# H1FR50.net
KiCad netlist of a schematic drawn in EAGLE
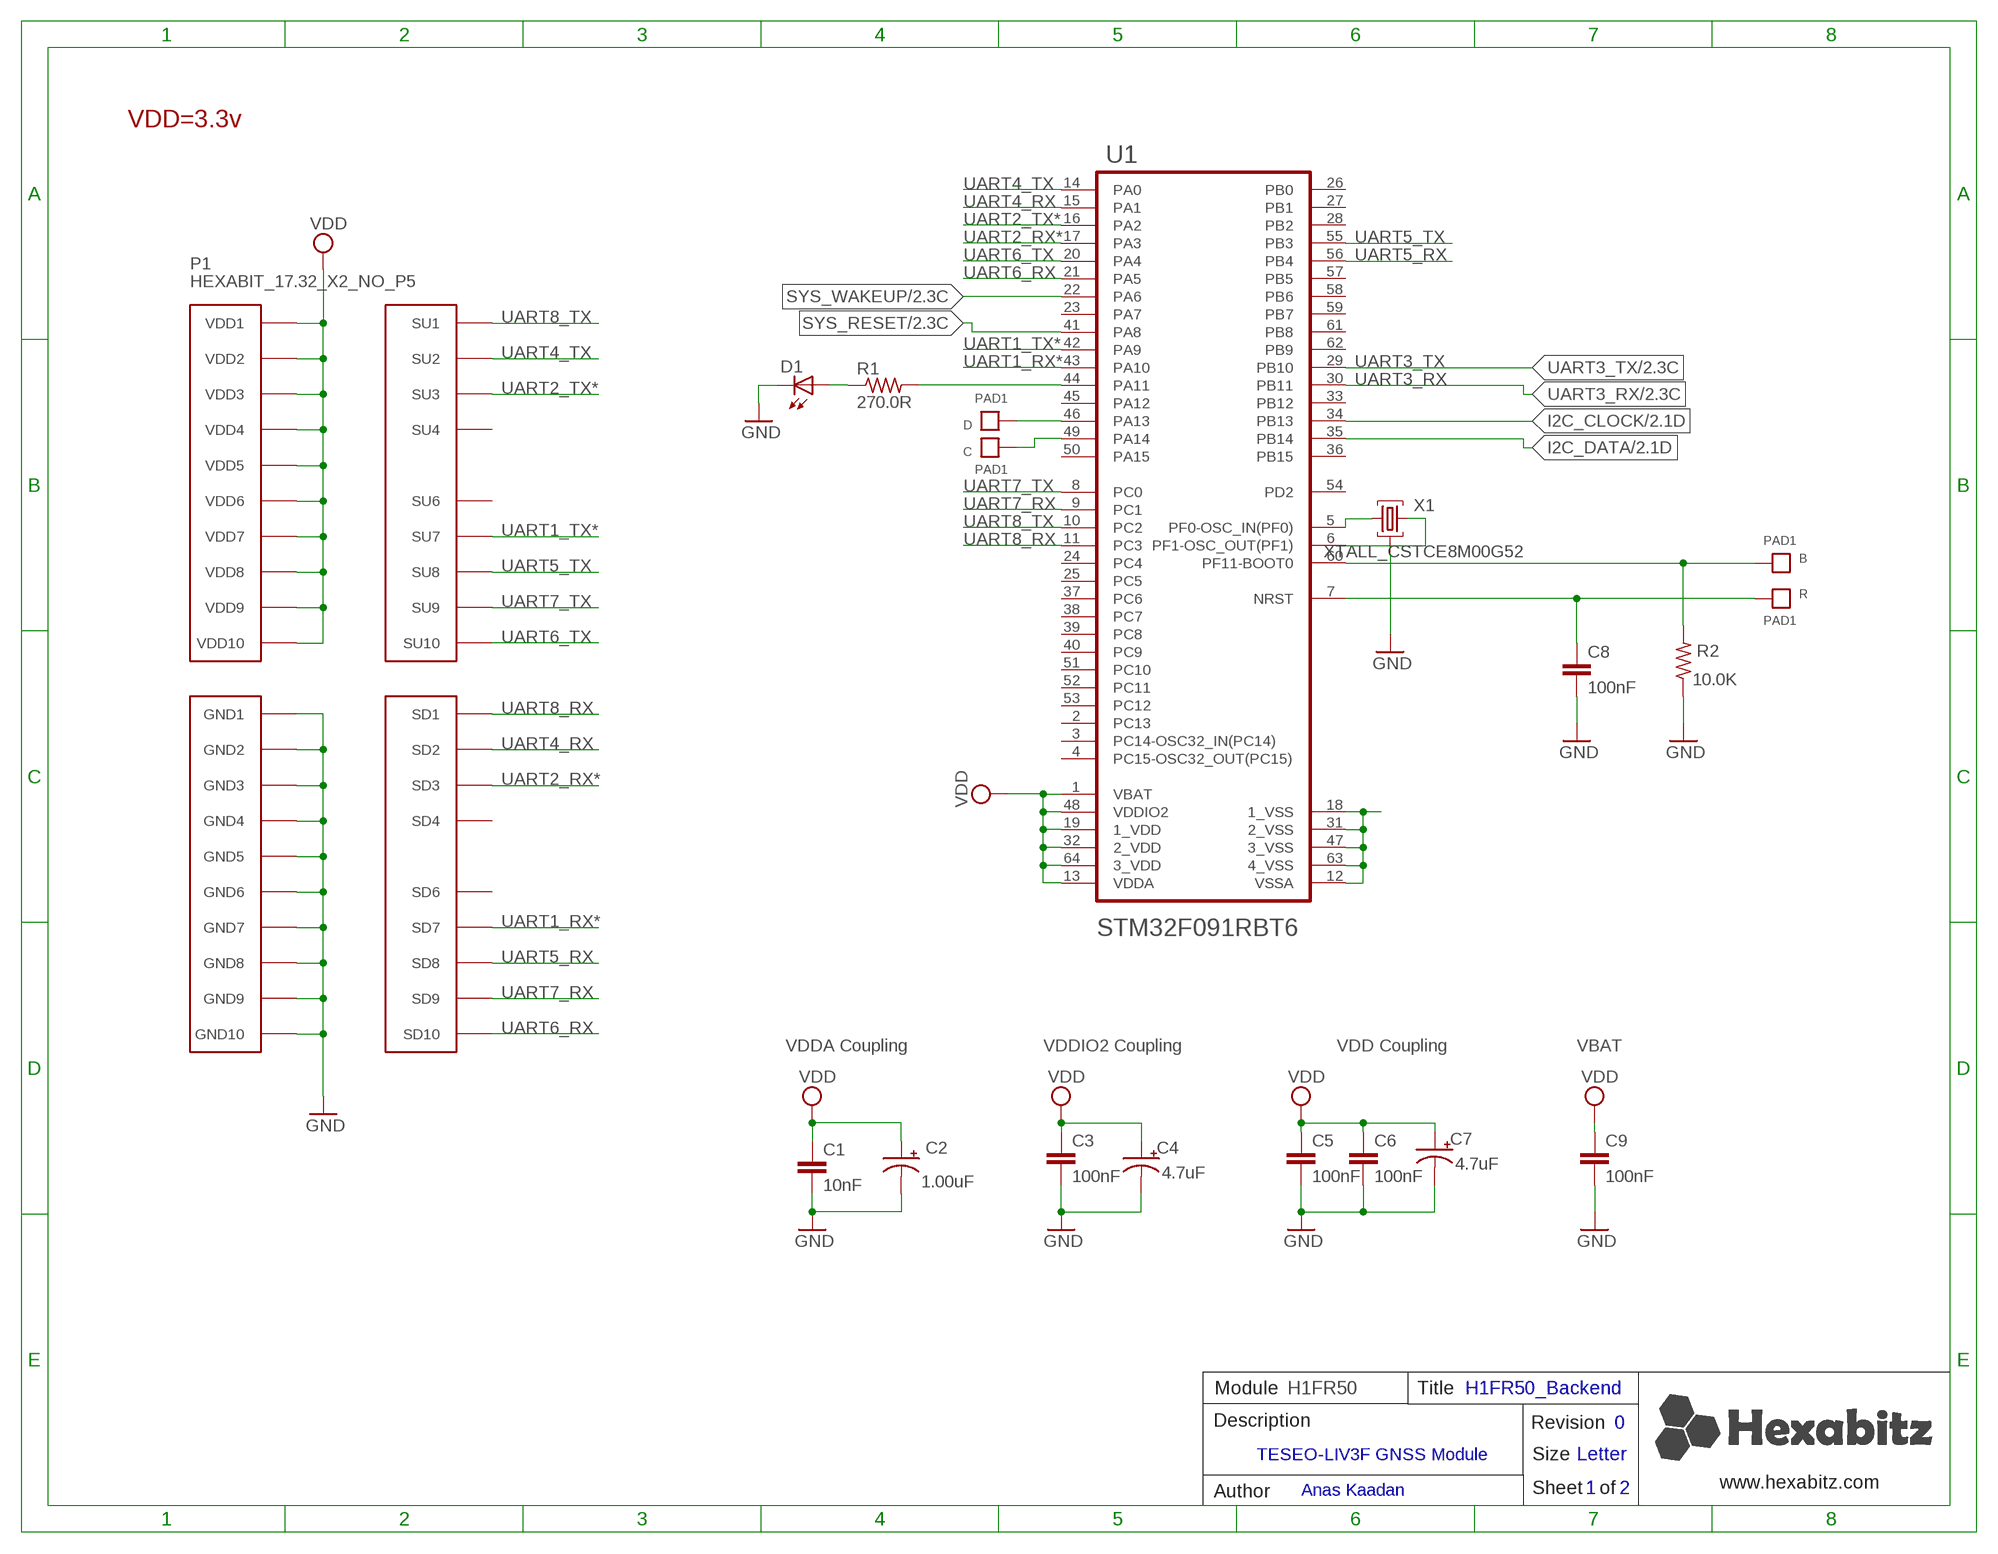
[diagram p0: schematic, sheet 1]
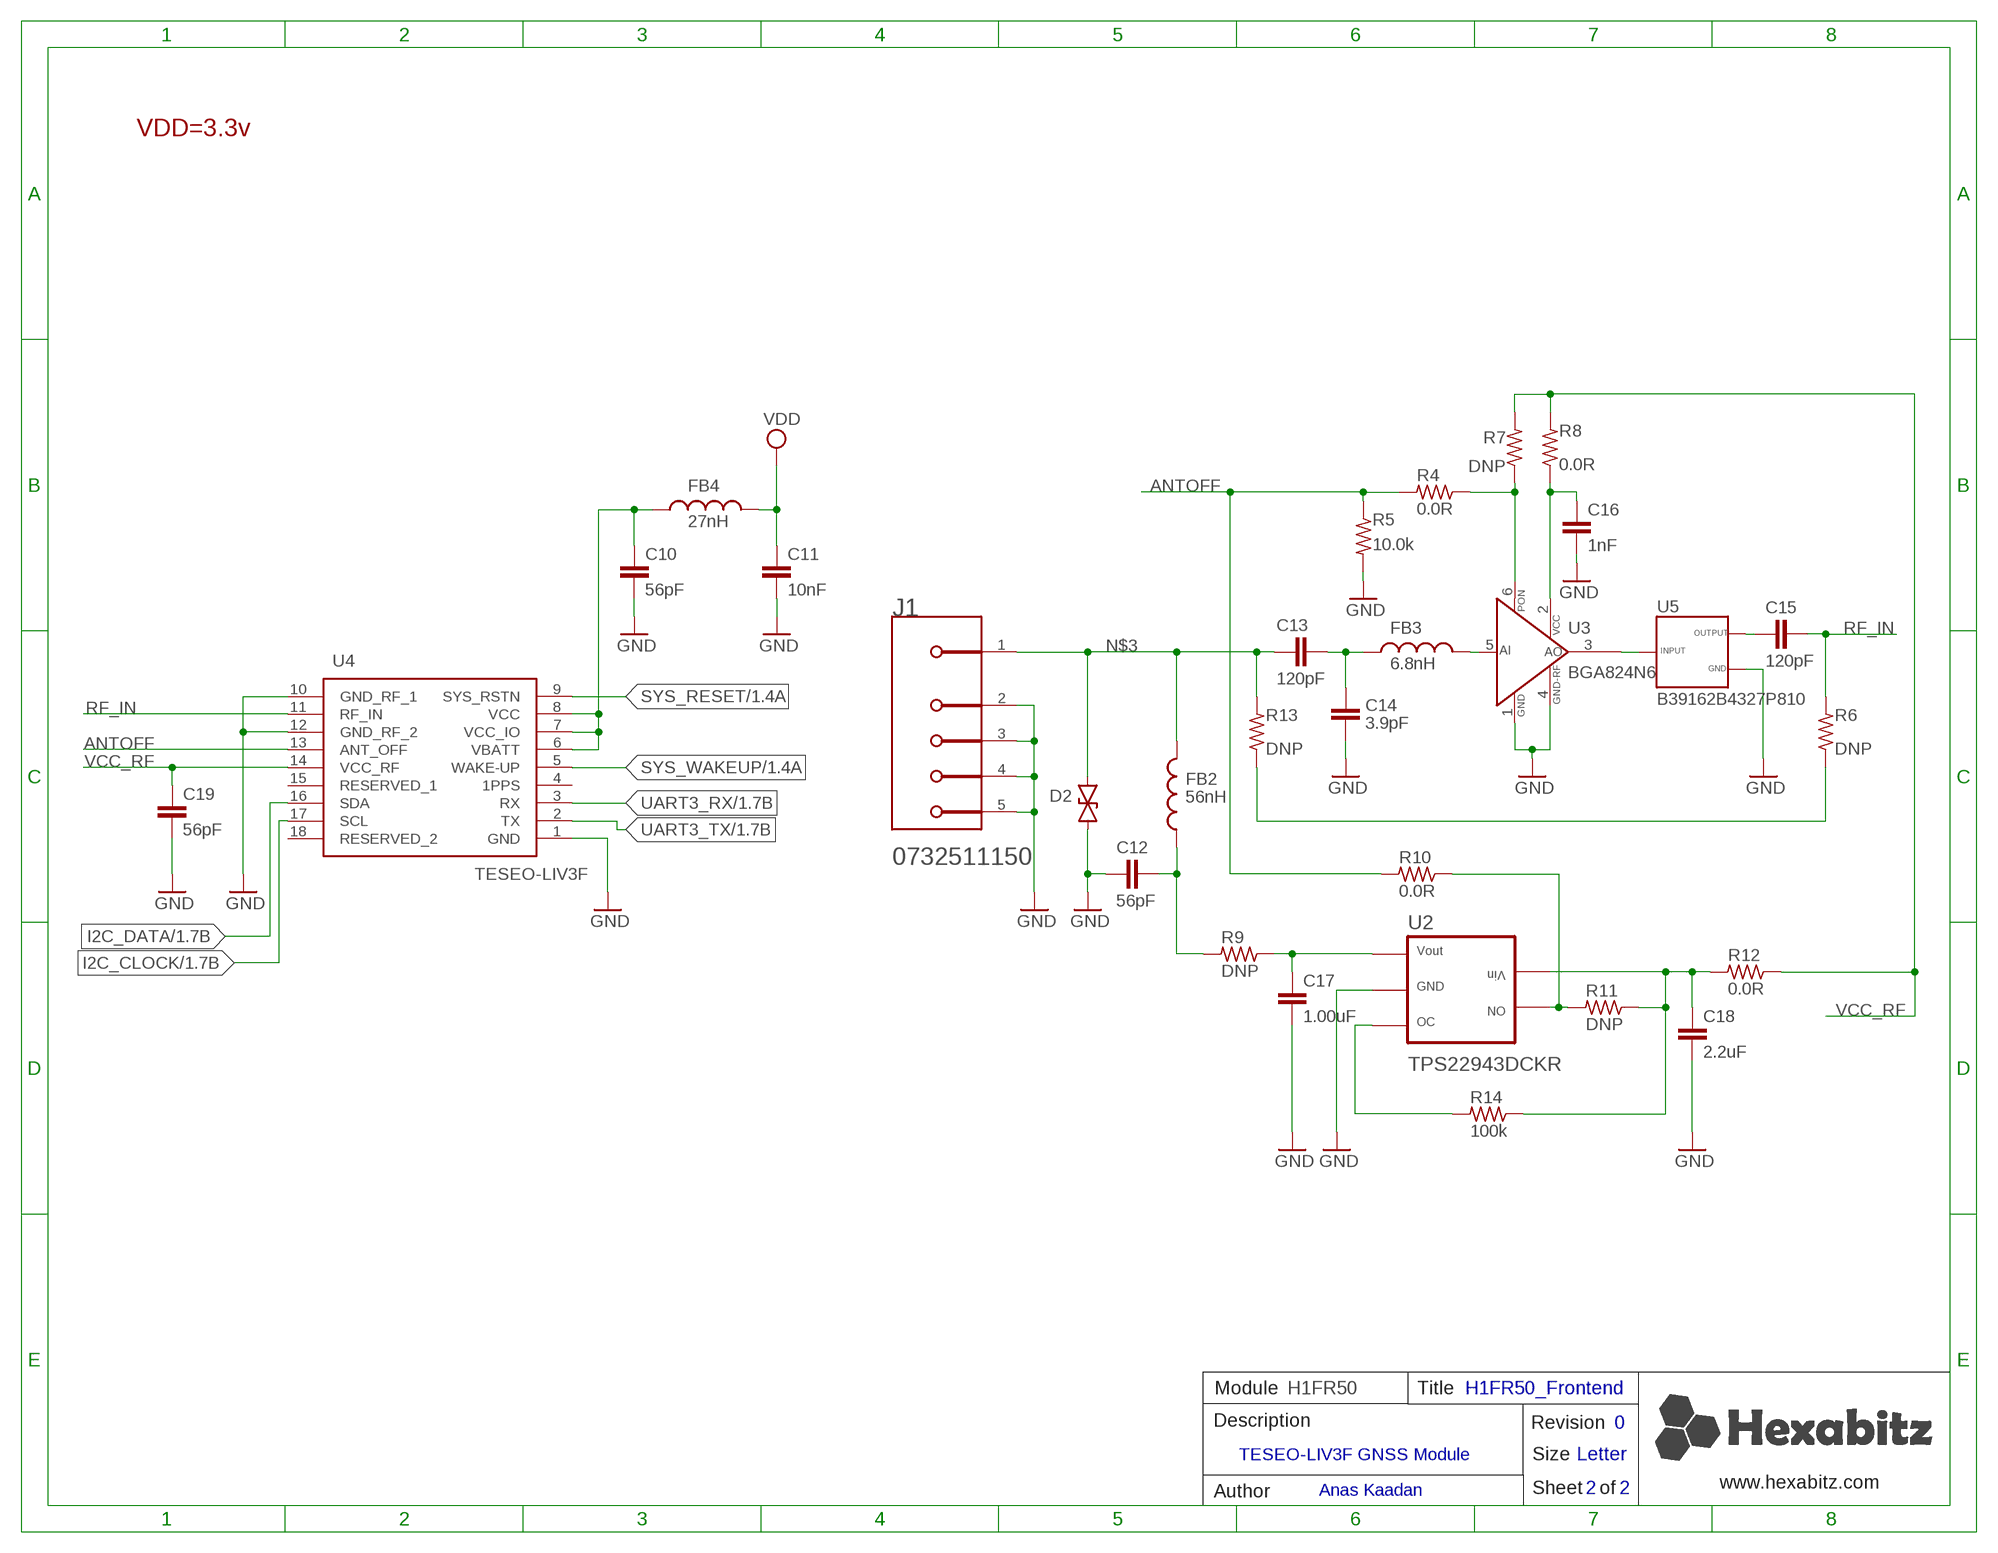
[diagram p1: schematic, sheet 2]

(export (version "E")
  (design (tool "Eeschema 10.0.6"))
  (components
    (comp (ref "C10")
      (value "56pF")
      (footprint "eagle-import:C-0201")
      (fields
        (field (name "MFN") "Murata")
        (field (name "MPN") "GRM0335C1E560GA01D")
        (field (name "OCTOPART_URL") "https://octopart.com/grm0335c1e560ga01d-murata-24611383?r=sp")
      )
      (libsource (lib "eagle-import") (part "C-0201C0201"))
    )
    (comp (ref "C11")
      (value "10nF")
      (footprint "eagle-import:C-0402")
      (fields
        (field (name "CAPACITANCE") "10nF ")
        (field (name "MFN") "TDK ")
        (field (name "MPN") "CGA2B3X7R1H103K050BE ")
        (field (name "OCTOPART_URL") "https://octopart.com/cga2b3x7r1h103k050be-tdk-68305469?r=sp ")
      )
      (libsource (lib "eagle-import") (part "C-0402"))
    )
    (comp (ref "C12")
      (value "56pF")
      (footprint "eagle-import:C-0402")
      (fields
        (field (name "CAPACITANCE") "56pF ")
        (field (name "MFN") "Murata ")
        (field (name "MPN") "GRM1555C1H560JA01D ")
        (field (name "OCTOPART_URL") "https://octopart.com/grm1555c1h560ja01d-murata-15197568?r=sp ")
      )
      (libsource (lib "eagle-import") (part "C-0402"))
    )
    (comp (ref "C13")
      (value "120pF")
      (footprint "eagle-import:C-0402")
      (fields
        (field (name "CAPACITANCE") "120pF ")
        (field (name "MFN") "Murata ")
        (field (name "MPN") "GRM1555C1H121JA01D ")
        (field (name "OCTOPART_URL") "https://octopart.com/grm1555c1h121ja01d-murata-196010?r=sp ")
      )
      (libsource (lib "eagle-import") (part "C-0402"))
    )
    (comp (ref "C14")
      (value "3.9pF")
      (footprint "eagle-import:C-0402")
      (fields
        (field (name "CAPACITANCE") "3.9pF ")
        (field (name "MFN") "Murata ")
        (field (name "MPN") "GRM1555C1H3R9WA01D ")
        (field (name "OCTOPART_URL") "https://octopart.com/grm1555c1h3r9wa01d-murata-20477997?r=sp ")
      )
      (libsource (lib "eagle-import") (part "C-0402"))
    )
    (comp (ref "C15")
      (value "120pF")
      (footprint "eagle-import:C-0402")
      (fields
        (field (name "CAPACITANCE") "120pF ")
        (field (name "MFN") "Murata ")
        (field (name "MPN") "GRM1555C1H121JA01D ")
        (field (name "OCTOPART_URL") "https://octopart.com/grm1555c1h121ja01d-murata-196010?r=sp ")
      )
      (libsource (lib "eagle-import") (part "C-0402"))
    )
    (comp (ref "C16")
      (value "1nF")
      (footprint "eagle-import:C-0402")
      (fields
        (field (name "CAPACITANCE") "1nF ")
        (field (name "MFN") "Murata ")
        (field (name "MPN") "GRM155R71H102KA01D ")
        (field (name "OCTOPART_URL") "https://octopart.com/grm155r71h102ka01d-murata-196021?r=sp ")
      )
      (libsource (lib "eagle-import") (part "C-0402"))
    )
    (comp (ref "C17")
      (value "1.00uF")
      (footprint "eagle-import:C-0402")
      (fields
        (field (name "CAPACITANCE") "1.00uF")
        (field (name "MFN") "KEMET")
        (field (name "MPN") "C0402C105K8PAC7411")
        (field (name "OCTOPART_URL") "https://octopart.com/c0402c105k8pac7411-kemet-75146233?r=sp")
      )
      (libsource (lib "eagle-import") (part "C-0402"))
    )
    (comp (ref "C18")
      (value "2.2uF")
      (footprint "eagle-import:C-0402")
      (fields
        (field (name "CAPACITANCE") "2.2uF")
        (field (name "MFN") "https://octopart.com/c0402c225k7pactu-kemet-89187402?r=sp")
        (field (name "MPN") "C0402C225K7PACTU")
        (field (name "OCTOPART_URL") "https://octopart.com/c0402c225k7pactu-kemet-89187402?r=sp")
      )
      (libsource (lib "eagle-import") (part "C-0402"))
    )
    (comp (ref "C19")
      (value "56pF")
      (footprint "eagle-import:C-0201")
      (fields
        (field (name "MFN") "Murata")
        (field (name "MPN") "GRM0335C1E560GA01D")
        (field (name "OCTOPART_URL") "https://octopart.com/grm0335c1e560ga01d-murata-24611383?r=sp")
      )
      (libsource (lib "eagle-import") (part "C-0201C0201"))
    )
    (comp (ref "D2")
      (value "ESDARF02-1BU2CK")
      (footprint "eagle-import:CAPC0201X13N")
      (libsource (lib "eagle-import") (part "ESDARF02-1BU2CK"))
    )
    (comp (ref "FB2")
      (value "56nH")
      (footprint "eagle-import:FB-0402")
      (fields (field (name "MFN") "Murata ") (field (name "MPN") "LQW15AN6N8G00D "))
      (libsource (lib "eagle-import") (part "FB-0402"))
    )
    (comp (ref "FB3")
      (value "6.8nH")
      (footprint "eagle-import:FB-0402")
      (fields (field (name "MFN") "Würth Elektronik ") (field (name "MPN") "744784156A "))
      (libsource (lib "eagle-import") (part "FB-0402"))
    )
    (comp (ref "FB4")
      (value "27nH")
      (footprint "eagle-import:FB-0402")
      (fields (field (name "MFN") "Murata ") (field (name "MPN") "LQG15HS27NJ02D "))
      (libsource (lib "eagle-import") (part "FB-0402"))
    )
    (comp (ref "J1")
      (value "MOLEX_INC_0732511150MOLEX_INC_0732511150_0_0")
      (footprint "eagle-import:MOLEX_INC_0732511150_0")
      (fields
        (field (name "DIGIKEY_PART_NUMBER") "WM5534-ND")
        (field (name "MF") "Molex Inc")
        (field (name "MPN") "0732511150")
      )
      (libsource (lib "eagle-import") (part "MOLEX_INC_0732511150MOLEX_INC_0732511150_0_0"))
    )
    (comp (ref "R4")
      (value "0.0R")
      (footprint "eagle-import:R-0402")
      (libsource (lib "eagle-import") (part "R-0402"))
    )
    (comp (ref "R5")
      (value "10.0k")
      (footprint "eagle-import:R-0402")
      (fields
        (field (name "MFN") "TE Connectivity")
        (field (name "MPN") "CRGCQ0402F10K")
        (field (name "OCTOPART_URL") "https://octopart.com/crgcq0402f10k-te+connectivity-91017932?r=sp ")
        (field (name "RESISTANCE") "10.0K ")
        (field (name "TOLERANCE") "±1% ")
      )
      (libsource (lib "eagle-import") (part "R-0402"))
    )
    (comp (ref "R6")
      (value "DNP")
      (footprint "eagle-import:R-0402")
      (libsource (lib "eagle-import") (part "R-0402"))
    )
    (comp (ref "R7")
      (value "DNP")
      (footprint "eagle-import:R-0402")
      (libsource (lib "eagle-import") (part "R-0402"))
    )
    (comp (ref "R8")
      (value "0.0R")
      (footprint "eagle-import:R-0402")
      (libsource (lib "eagle-import") (part "R-0402"))
    )
    (comp (ref "R9")
      (value "DNP")
      (footprint "eagle-import:R-0402")
      (libsource (lib "eagle-import") (part "R-0402"))
    )
    (comp (ref "R10")
      (value "0.0R")
      (footprint "eagle-import:R-0402")
      (libsource (lib "eagle-import") (part "R-0402"))
    )
    (comp (ref "R11")
      (value "DNP")
      (footprint "eagle-import:R-0402")
      (libsource (lib "eagle-import") (part "R-0402"))
    )
    (comp (ref "R12")
      (value "0.0R")
      (footprint "eagle-import:R-0402")
      (libsource (lib "eagle-import") (part "R-0402"))
    )
    (comp (ref "R13")
      (value "DNP")
      (footprint "eagle-import:R-0402")
      (libsource (lib "eagle-import") (part "R-0402"))
    )
    (comp (ref "R14")
      (value "100k")
      (footprint "eagle-import:R-0603")
      (fields
        (field (name "MFN") "Yageo ")
        (field (name "MPN") "AC0603FR-07100KL ")
        (field (name "OCTOPART_URL") "https://octopart.com/ac0603fr-07100kl-yageo-21711090?r=sp ")
        (field (name "RESISTANCE") "100k ")
        (field (name "TOLERANCE") "±1% ")
      )
      (libsource (lib "eagle-import") (part "R-0603"))
    )
    (comp (ref "U2")
      (value "TPS22943DCKR")
      (footprint "eagle-import:SOT65P210X110-5N")
      (libsource (lib "eagle-import") (part "TPS22943DCKR"))
    )
    (comp (ref "U3")
      (value "BGA824N6")
      (footprint "eagle-import:BGA824N6")
      (fields (field (name "MPN") "BGA824N6E6327XTSA1"))
      (libsource (lib "eagle-import") (part "BGA824N6"))
    )
    (comp (ref "U4")
      (value "TESEO-LIV3F")
      (footprint "eagle-import:SON110P970X1010X230-18N")
      (fields (field (name "MF") "STMicroelectronics"))
      (libsource (lib "eagle-import") (part "TESEO-LIV3F"))
    )
    (comp (ref "U5")
      (value "B39162B4327P810")
      (footprint "eagle-import:FIL_B39162B4327P810")
      (libsource (lib "eagle-import") (part "B39162B4327P810"))
    )
    (comp (ref "B")
      (value "PAD1")
      (footprint "eagle-import:PAD1")
      (libsource (lib "eagle-import") (part "PAD1"))
    )
    (comp (ref "C")
      (value "PAD1")
      (footprint "eagle-import:PAD1")
      (libsource (lib "eagle-import") (part "PAD1"))
    )
    (comp (ref "C1")
      (value "10nF")
      (footprint "eagle-import:C-0603")
      (fields
        (field (name "CAPACITANCE") "10nF")
        (field (name "MFN") "KEMET")
        (field (name "MPN") "C0603C103K5RACTU")
        (field (name "OCTOPART_URL") "https://octopart.com/c0603c103k5ractu-kemet-133094?r=sp&s=R_iPBxLnSmGqhkU2rIMFpg")
        (field (name "TOLERANCE") "10%")
        (field (name "VOLTAGE_RATING") "50V")
      )
      (libsource (lib "eagle-import") (part "C-0603"))
    )
    (comp (ref "C2")
      (value "1.00uF")
      (footprint "eagle-import:C-0805-POL")
      (fields
        (field (name "CAPACITANCE") "1.00uF")
        (field (name "MFN") "Yageo")
        (field (name "MPN") "CC0805KKX7R7BB105")
        (field (name "OCTOPART_URL") "https://octopart.com/cc0805kkx7r7bb105-yageo-8376555?r=sp&s=YKl1wwtkROau_X5nniH2ig")
        (field (name "TOLERANCE") "10%")
        (field (name "VOLTAGE_RATING") "16V")
      )
      (libsource (lib "eagle-import") (part "C-0805-POL"))
    )
    (comp (ref "C3")
      (value "100nF")
      (footprint "eagle-import:C-0603")
      (fields
        (field (name "CAPACITANCE") "100nF")
        (field (name "MFN") "KEMET")
        (field (name "MPN") "C0603C104K8RACTU")
        (field (name "OCTOPART_URL") "https://octopart.com/c0603c104k8ractu-kemet-145075?r=sp&s=9bS9ASSwSEqMCE9KBEQZ0g")
        (field (name "TOLERANCE") "10%")
        (field (name "VOLTAGE_RATING") "10V")
      )
      (libsource (lib "eagle-import") (part "C-0603"))
    )
    (comp (ref "C4")
      (value "4.7uF")
      (footprint "eagle-import:C-0805-POL")
      (fields
        (field (name "CAPACITANCE") "4.7uF")
        (field (name "MFN") "Murata")
        (field (name "MPN") "GRM21BC81E475KA12L")
        (field (name "OCTOPART_URL") "https://octopart.com/grm21bc81e475ka12l-murata-10331911?r=sp&s=RY3qZSD8T6mG6TC9CHI5qQ")
        (field (name "TOLERANCE") "10%")
        (field (name "VOLTAGE_RATING") "25V")
      )
      (libsource (lib "eagle-import") (part "C-0805-POL"))
    )
    (comp (ref "C5")
      (value "100nF")
      (footprint "eagle-import:C-0603")
      (fields
        (field (name "CAPACITANCE") "100nF")
        (field (name "MFN") "KEMET")
        (field (name "MPN") "C0603C104K8RACTU")
        (field (name "OCTOPART_URL") "https://octopart.com/c0603c104k8ractu-kemet-145075?r=sp&s=9bS9ASSwSEqMCE9KBEQZ0g")
        (field (name "TOLERANCE") "10%")
        (field (name "VOLTAGE_RATING") "10")
      )
      (libsource (lib "eagle-import") (part "C-0603"))
    )
    (comp (ref "C6")
      (value "100nF")
      (footprint "eagle-import:C-0603")
      (fields
        (field (name "CAPACITANCE") "100nF")
        (field (name "MFN") "KEMET")
        (field (name "MPN") "C0603C104K8RACTU")
        (field (name "OCTOPART_URL") "https://octopart.com/c0603c104k8ractu-kemet-145075?r=sp&s=9bS9ASSwSEqMCE9KBEQZ0g")
        (field (name "TOLERANCE") "10%")
        (field (name "VOLTAGE_RATING") "10V")
      )
      (libsource (lib "eagle-import") (part "C-0603"))
    )
    (comp (ref "C7")
      (value "4.7uF")
      (footprint "eagle-import:C-0805-POL")
      (fields
        (field (name "CAPACITANCE") "4.7uF")
        (field (name "MFN") "Murata")
        (field (name "MPN") "GRM21BC81E475KA12L")
        (field (name "OCTOPART_URL") "https://octopart.com/grm21bc81e475ka12l-murata-10331911?r=sp&s=RY3qZSD8T6mG6TC9CHI5qQ")
        (field (name "TOLERANCE") "10%")
        (field (name "VOLTAGE_RATING") "25V")
      )
      (libsource (lib "eagle-import") (part "C-0805-POL"))
    )
    (comp (ref "C8")
      (value "100nF")
      (footprint "eagle-import:C-0603")
      (fields
        (field (name "CAPACITANCE") "100nF")
        (field (name "MFN") "KEMET")
        (field (name "MPN") "C0603C104K8RACTU")
        (field (name "OCTOPART_URL") "https://octopart.com/c0603c104k8ractu-kemet-145075?r=sp&s=9bS9ASSwSEqMCE9KBEQZ0g")
        (field (name "TOLERANCE") "10%")
        (field (name "VOLTAGE_RATING") "10V")
      )
      (libsource (lib "eagle-import") (part "C-0603"))
    )
    (comp (ref "C9")
      (value "100nF")
      (footprint "eagle-import:C-0603")
      (fields
        (field (name "CAPACITANCE") "100nF")
        (field (name "MFN") "KEMET")
        (field (name "MPN") "C0603C104K8RACTU")
        (field (name "OCTOPART_URL") "https://octopart.com/c0603c104k8ractu-kemet-145075?r=sp&s=9bS9ASSwSEqMCE9KBEQZ0g")
        (field (name "TOLERANCE") "10V")
        (field (name "VOLTAGE_RATING") "10%")
      )
      (libsource (lib "eagle-import") (part "C-0603"))
    )
    (comp (ref "D")
      (value "PAD1")
      (footprint "eagle-import:PAD1")
      (libsource (lib "eagle-import") (part "PAD1"))
    )
    (comp (ref "D1")
      (value "VLMS1300-GS08")
      (footprint "eagle-import:VLMS1300-GS08")
      (fields
        (field (name "MFN") "Vishay")
        (field (name "MPN") "VLMS1300-GS08")
        (field (name "OCTOPART_URL") "https://octopart.com/vlms1300-gs08-vishay-21709201?r=sp&s=_gcP4_q8T1SC6PJQPTQ9yA")
      )
      (libsource (lib "eagle-import") (part "VLMS1300-GS08"))
    )
    (comp (ref "P1")
      (value "HEXABIT_17.32_X2_NO_P5")
      (footprint "eagle-import:HEXABIT_17.32_X2_NO_P5")
      (libsource (lib "eagle-import") (part "HEXABIT_?_X2_NO_P517.32"))
    )
    (comp (ref "R")
      (value "PAD1")
      (footprint "eagle-import:PAD1")
      (libsource (lib "eagle-import") (part "PAD1"))
    )
    (comp (ref "R1")
      (value "270.0R")
      (footprint "eagle-import:R-0603")
      (fields
        (field (name "MFN") "Yageo")
        (field (name "MPN") "RC0603FR-07270RL")
        (field (name "OCTOPART_URL") "https://octopart.com/search?q=RC0603FR-07270RL&start=0")
        (field (name "RESISTANCE") "270.0 Ohm")
        (field (name "TOLERANCE") "1%")
      )
      (libsource (lib "eagle-import") (part "Hexabitz_R-0603"))
    )
    (comp (ref "R2")
      (value "10.0K")
      (footprint "eagle-import:R-0603")
      (fields
        (field (name "MFN") "Yageo")
        (field (name "MPN") "RC0603JR-0710KL")
        (field (name "OCTOPART_URL") "https://octopart.com/search?q=RC0603JR-0710KL&start=0")
        (field (name "RESISTANCE") "10.0K Ohm")
        (field (name "TOLERANCE") "5%")
      )
      (libsource (lib "eagle-import") (part "Hexabitz_R-0603"))
    )
    (comp (ref "U1")
      (value "STM32F091RBT6STMICROELECTRONICS_STM32F091RBT6_0_1")
      (footprint "eagle-import:STMICROELECTRONICS_STM32F091RBT6_1")
      (fields (field (name "MF") "STMicroelectronics") (field (name "MPN") "STM32F091RBT6"))
      (libsource (lib "eagle-import") (part "STM32F091RBT6STMICROELECTRONICS_STM32F091RBT6_0_1"))
    )
    (comp (ref "X1")
      (value "XTALL_CSTCE8M00G52")
      (footprint "eagle-import:XTALL_CSTCE8M00G52")
      (fields (field (name "MPN") "CSTCE8M00G52Z-R0"))
      (libsource (lib "eagle-import") (part "XTALL_CSTCE8M00G52"))
    )
  )
  (nets
    (net (code "1") (name "ANTOFF") (class "Default")
      (node (ref "R10") (pin "2") (pinfunction "2_2") (pintype "passive"))
      (node (ref "R4") (pin "2") (pinfunction "2_2") (pintype "passive"))
      (node (ref "R5") (pin "1") (pinfunction "1_1") (pintype "passive"))
      (node (ref "U4") (pin "13") (pinfunction "ANT_OFF_13") (pintype "bidirectional"))
    )
    (net (code "2") (name "GND") (class "Default")
      (node (ref "C1") (pin "2") (pinfunction "2_2") (pintype "passive"))
      (node (ref "C10") (pin "1") (pinfunction "1_1") (pintype "passive"))
      (node (ref "C11") (pin "1") (pinfunction "1_1") (pintype "passive"))
      (node (ref "C12") (pin "1") (pinfunction "1_1") (pintype "passive"))
      (node (ref "C14") (pin "1") (pinfunction "1_1") (pintype "passive"))
      (node (ref "C16") (pin "2") (pinfunction "2_2") (pintype "passive"))
      (node (ref "C17") (pin "2") (pinfunction "2_2") (pintype "passive"))
      (node (ref "C18") (pin "2") (pinfunction "2_2") (pintype "passive"))
      (node (ref "C19") (pin "1") (pinfunction "1_1") (pintype "passive"))
      (node (ref "C2") (pin "2") (pinfunction "-_2") (pintype "passive"))
      (node (ref "C3") (pin "2") (pinfunction "2_2") (pintype "passive"))
      (node (ref "C4") (pin "2") (pinfunction "-_2") (pintype "passive"))
      (node (ref "C5") (pin "2") (pinfunction "2_2") (pintype "passive"))
      (node (ref "C6") (pin "2") (pinfunction "2_2") (pintype "passive"))
      (node (ref "C7") (pin "2") (pinfunction "-_2") (pintype "passive"))
      (node (ref "C8") (pin "2") (pinfunction "2_2") (pintype "passive"))
      (node (ref "C9") (pin "2") (pinfunction "2_2") (pintype "passive"))
      (node (ref "D1") (pin "C") (pinfunction "C_C") (pintype "passive"))
      (node (ref "D2") (pin "1") (pinfunction "1_1") (pintype "passive"))
      (node (ref "J1") (pin "2") (pinfunction "MNT_1_2") (pintype "passive"))
      (node (ref "J1") (pin "3") (pinfunction "MNT_2_3") (pintype "passive"))
      (node (ref "J1") (pin "4") (pinfunction "MNT_3_4") (pintype "passive"))
      (node (ref "J1") (pin "5") (pinfunction "MNT_4_5") (pintype "passive"))
      (node (ref "P1") (pin "PAD_PD11") (pinfunction "GND1_PAD_PD11") (pintype "power_in"))
      (node (ref "P1") (pin "PAD_PD12") (pinfunction "GND2_PAD_PD12") (pintype "power_in"))
      (node (ref "P1") (pin "PAD_PD13") (pinfunction "GND3_PAD_PD13") (pintype "power_in"))
      (node (ref "P1") (pin "PAD_PD14") (pinfunction "GND4_PAD_PD14") (pintype "power_in"))
      (node (ref "P1") (pin "PAD_PD15") (pinfunction "GND5_PAD_PD15") (pintype "power_in"))
      (node (ref "P1") (pin "PAD_PD16") (pinfunction "GND6_PAD_PD16") (pintype "power_in"))
      (node (ref "P1") (pin "PAD_PD17") (pinfunction "GND7_PAD_PD17") (pintype "power_in"))
      (node (ref "P1") (pin "PAD_PD18") (pinfunction "GND8_PAD_PD18") (pintype "power_in"))
      (node (ref "P1") (pin "PAD_PD19") (pinfunction "GND9_PAD_PD19") (pintype "power_in"))
      (node (ref "P1") (pin "PAD_PD20") (pinfunction "GND10_PAD_PD20") (pintype "power_in"))
      (node (ref "R2") (pin "1") (pinfunction "1_1") (pintype "passive"))
      (node (ref "R5") (pin "2") (pinfunction "2_2") (pintype "passive"))
      (node (ref "U1") (pin "12") (pinfunction "VSSA_12") (pintype "power_in"))
      (node (ref "U1") (pin "18") (pinfunction "1_VSS_18") (pintype "power_in"))
      (node (ref "U1") (pin "31") (pinfunction "2_VSS_31") (pintype "power_in"))
      (node (ref "U1") (pin "47") (pinfunction "3_VSS_47") (pintype "power_in"))
      (node (ref "U1") (pin "63") (pinfunction "4_VSS_63") (pintype "power_in"))
      (node (ref "U2") (pin "2") (pinfunction "GND_2") (pintype "power_in"))
      (node (ref "U3") (pin "1") (pinfunction "GND_1") (pintype "input"))
      (node (ref "U3") (pin "4") (pinfunction "GND-RF_4") (pintype "passive"))
      (node (ref "U4") (pin "1") (pinfunction "GND_1") (pintype "bidirectional"))
      (node (ref "U4") (pin "10") (pinfunction "GND_RF_1_10") (pintype "bidirectional"))
      (node (ref "U4") (pin "12") (pinfunction "GND_RF_2_12") (pintype "bidirectional"))
      (node (ref "U5") (pin "2") (pinfunction "GND_2") (pintype "power_in"))
      (node (ref "U5") (pin "3") (pinfunction "GND_3") (pintype "power_in"))
      (node (ref "U5") (pin "5") (pinfunction "GND_5") (pintype "power_in"))
      (node (ref "X1") (pin "P$2") (pinfunction "2_P$2") (pintype "passive"))
    )
    (net (code "3") (name "I2C_CLOCK") (class "Default")
      (node (ref "U1") (pin "34") (pinfunction "PB13_34") (pintype "bidirectional"))
      (node (ref "U4") (pin "17") (pinfunction "SCL_17") (pintype "bidirectional"))
    )
    (net (code "4") (name "I2C_DATA") (class "Default")
      (node (ref "U1") (pin "35") (pinfunction "PB14_35") (pintype "bidirectional"))
      (node (ref "U4") (pin "16") (pinfunction "SDA_16") (pintype "bidirectional"))
    )
    (net (code "5") (name "N$3") (class "Default")
      (node (ref "C13") (pin "1") (pinfunction "1_1") (pintype "passive"))
      (node (ref "D2") (pin "2") (pinfunction "2_2") (pintype "passive"))
      (node (ref "FB2") (pin "2") (pinfunction "2_2") (pintype "passive"))
      (node (ref "J1") (pin "1") (pinfunction "1_1") (pintype "passive"))
      (node (ref "R13") (pin "2") (pinfunction "2_2") (pintype "passive"))
    )
    (net (code "6") (name "Net-(C12-Pad2)") (class "Default")
      (node (ref "C12") (pin "2") (pinfunction "2_2") (pintype "passive"))
      (node (ref "FB2") (pin "1") (pinfunction "1_1") (pintype "passive"))
      (node (ref "R9") (pin "2") (pinfunction "2_2") (pintype "passive"))
    )
    (net (code "7") (name "Net-(C13-Pad2)") (class "Default")
      (node (ref "C13") (pin "2") (pinfunction "2_2") (pintype "passive"))
      (node (ref "C14") (pin "2") (pinfunction "2_2") (pintype "passive"))
      (node (ref "FB3") (pin "1") (pinfunction "1_1") (pintype "passive"))
    )
    (net (code "8") (name "Net-(D1-PadA)") (class "Default")
      (node (ref "D1") (pin "A") (pinfunction "A_A") (pintype "passive"))
      (node (ref "R1") (pin "1") (pinfunction "1_1") (pintype "passive"))
    )
    (net (code "9") (name "Net-(R13-Pad1)") (class "Default")
      (node (ref "R13") (pin "1") (pinfunction "1_1") (pintype "passive"))
      (node (ref "R6") (pin "1") (pinfunction "1_1") (pintype "passive"))
    )
    (net (code "10") (name "Net-(U1-NRST)") (class "Default")
      (node (ref "C8") (pin "1") (pinfunction "1_1") (pintype "passive"))
      (node (ref "R") (pin "P$1") (pinfunction "P$1_P$1") (pintype "passive"))
      (node (ref "R") (pin "P$2") (pinfunction "P$1_P$2") (pintype "passive"))
      (node (ref "U1") (pin "7") (pinfunction "NRST_7") (pintype "bidirectional"))
    )
    (net (code "11") (name "Net-(U1-PA11)") (class "Default")
      (node (ref "R1") (pin "2") (pinfunction "2_2") (pintype "passive"))
      (node (ref "U1") (pin "44") (pinfunction "PA11_44") (pintype "bidirectional"))
    )
    (net (code "12") (name "Net-(U1-PA13)") (class "Default")
      (node (ref "D") (pin "P$1") (pinfunction "P$1_P$1") (pintype "passive"))
      (node (ref "D") (pin "P$2") (pinfunction "P$1_P$2") (pintype "passive"))
      (node (ref "U1") (pin "46") (pinfunction "PA13_46") (pintype "bidirectional"))
    )
    (net (code "13") (name "Net-(U1-PA14)") (class "Default")
      (node (ref "C") (pin "P$1") (pinfunction "P$1_P$1") (pintype "passive"))
      (node (ref "C") (pin "P$2") (pinfunction "P$1_P$2") (pintype "passive"))
      (node (ref "U1") (pin "49") (pinfunction "PA14_49") (pintype "bidirectional"))
    )
    (net (code "14") (name "Net-(U1-PF0-OSC_IN(PF0))") (class "Default")
      (node (ref "U1") (pin "5") (pinfunction "PF0-OSC_IN(PF0)_5") (pintype "bidirectional"))
      (node (ref "X1") (pin "P$1") (pinfunction "1_P$1") (pintype "passive"))
    )
    (net (code "15") (name "Net-(U1-PF1-OSC_OUT(PF1))") (class "Default")
      (node (ref "U1") (pin "6") (pinfunction "PF1-OSC_OUT(PF1)_6") (pintype "bidirectional"))
      (node (ref "X1") (pin "P$3") (pinfunction "3_P$3") (pintype "passive"))
    )
    (net (code "16") (name "Net-(U1-PF11-BOOT0)") (class "Default")
      (node (ref "B") (pin "P$1") (pinfunction "P$1_P$1") (pintype "passive"))
      (node (ref "B") (pin "P$2") (pinfunction "P$1_P$2") (pintype "passive"))
      (node (ref "R2") (pin "2") (pinfunction "2_2") (pintype "passive"))
      (node (ref "U1") (pin "60") (pinfunction "PF11-BOOT0_60") (pintype "bidirectional"))
    )
    (net (code "17") (name "Net-(U2-OC)") (class "Default")
      (node (ref "R14") (pin "2") (pinfunction "2_2") (pintype "passive"))
      (node (ref "U2") (pin "3") (pinfunction "OC_3") (pintype "output"))
    )
    (net (code "18") (name "Net-(U2-ON)") (class "Default")
      (node (ref "R10") (pin "1") (pinfunction "1_1") (pintype "passive"))
      (node (ref "R11") (pin "2") (pinfunction "2_2") (pintype "passive"))
      (node (ref "U2") (pin "4") (pinfunction "ON_4") (pintype "input"))
    )
    (net (code "19") (name "Net-(U2-VIN)") (class "Default")
      (node (ref "C18") (pin "1") (pinfunction "1_1") (pintype "passive"))
      (node (ref "R11") (pin "1") (pinfunction "1_1") (pintype "passive"))
      (node (ref "R12") (pin "2") (pinfunction "2_2") (pintype "passive"))
      (node (ref "R14") (pin "1") (pinfunction "1_1") (pintype "passive"))
      (node (ref "U2") (pin "5") (pinfunction "VIN_5") (pintype "input"))
    )
    (net (code "20") (name "Net-(U2-VOUT)") (class "Default")
      (node (ref "C17") (pin "1") (pinfunction "1_1") (pintype "passive"))
      (node (ref "R9") (pin "1") (pinfunction "1_1") (pintype "passive"))
      (node (ref "U2") (pin "1") (pinfunction "VOUT_1") (pintype "output"))
    )
    (net (code "21") (name "Net-(U3-AI)") (class "Default")
      (node (ref "FB3") (pin "2") (pinfunction "2_2") (pintype "passive"))
      (node (ref "U3") (pin "5") (pinfunction "AI_5") (pintype "input"))
    )
    (net (code "22") (name "Net-(U3-AO)") (class "Default")
      (node (ref "U3") (pin "3") (pinfunction "AO_3") (pintype "output"))
      (node (ref "U5") (pin "1") (pinfunction "INPUT_1") (pintype "input"))
    )
    (net (code "23") (name "Net-(U3-PON)") (class "Default")
      (node (ref "R4") (pin "1") (pinfunction "1_1") (pintype "passive"))
      (node (ref "R7") (pin "1") (pinfunction "1_1") (pintype "passive"))
      (node (ref "U3") (pin "6") (pinfunction "PON_6") (pintype "input"))
    )
    (net (code "24") (name "Net-(U3-VCC)") (class "Default")
      (node (ref "C16") (pin "1") (pinfunction "1_1") (pintype "passive"))
      (node (ref "R8") (pin "1") (pinfunction "1_1") (pintype "passive"))
      (node (ref "U3") (pin "2") (pinfunction "VCC_2") (pintype "passive"))
    )
    (net (code "25") (name "Net-(U4-VBATT)") (class "Default")
      (node (ref "C10") (pin "2") (pinfunction "2_2") (pintype "passive"))
      (node (ref "FB4") (pin "1") (pinfunction "1_1") (pintype "passive"))
      (node (ref "U4") (pin "6") (pinfunction "VBATT_6") (pintype "bidirectional"))
      (node (ref "U4") (pin "7") (pinfunction "VCC_IO_7") (pintype "bidirectional"))
      (node (ref "U4") (pin "8") (pinfunction "VCC_8") (pintype "bidirectional"))
    )
    (net (code "26") (name "Net-(U5-OUTPUT)") (class "Default")
      (node (ref "C15") (pin "1") (pinfunction "1_1") (pintype "passive"))
      (node (ref "U5") (pin "4") (pinfunction "OUTPUT_4") (pintype "output"))
    )
    (net (code "27") (name "RF_IN") (class "Default")
      (node (ref "C15") (pin "2") (pinfunction "2_2") (pintype "passive"))
      (node (ref "R6") (pin "2") (pinfunction "2_2") (pintype "passive"))
      (node (ref "U4") (pin "11") (pinfunction "RF_IN_11") (pintype "bidirectional"))
    )
    (net (code "28") (name "SYS_RESET") (class "Default")
      (node (ref "U1") (pin "41") (pinfunction "PA8_41") (pintype "bidirectional"))
      (node (ref "U4") (pin "9") (pinfunction "SYS_RSTN_9") (pintype "bidirectional"))
    )
    (net (code "29") (name "SYS_WAKEUP") (class "Default")
      (node (ref "U1") (pin "22") (pinfunction "PA6_22") (pintype "bidirectional"))
      (node (ref "U4") (pin "5") (pinfunction "WAKE-UP_5") (pintype "bidirectional"))
    )
    (net (code "30") (name "UART1_RX*") (class "Default")
      (node (ref "P1") (pin "PAD_PD7") (pinfunction "SD7_PAD_PD7") (pintype "bidirectional"))
      (node (ref "U1") (pin "43") (pinfunction "PA10_43") (pintype "bidirectional"))
    )
    (net (code "31") (name "UART1_TX*") (class "Default")
      (node (ref "P1") (pin "PAD_PU7") (pinfunction "SU7_PAD_PU7") (pintype "bidirectional"))
      (node (ref "U1") (pin "42") (pinfunction "PA9_42") (pintype "bidirectional"))
    )
    (net (code "32") (name "UART2_RX*") (class "Default")
      (node (ref "P1") (pin "PAD_PD3") (pinfunction "SD3_PAD_PD3") (pintype "bidirectional"))
      (node (ref "U1") (pin "17") (pinfunction "PA3_17") (pintype "bidirectional"))
    )
    (net (code "33") (name "UART2_TX*") (class "Default")
      (node (ref "P1") (pin "PAD_PU3") (pinfunction "SU3_PAD_PU3") (pintype "bidirectional"))
      (node (ref "U1") (pin "16") (pinfunction "PA2_16") (pintype "bidirectional"))
    )
    (net (code "34") (name "UART3_RX") (class "Default")
      (node (ref "U1") (pin "30") (pinfunction "PB11_30") (pintype "bidirectional"))
      (node (ref "U4") (pin "3") (pinfunction "RX_3") (pintype "bidirectional"))
    )
    (net (code "35") (name "UART3_TX") (class "Default")
      (node (ref "U1") (pin "29") (pinfunction "PB10_29") (pintype "bidirectional"))
      (node (ref "U4") (pin "2") (pinfunction "TX_2") (pintype "bidirectional"))
    )
    (net (code "36") (name "UART4_RX") (class "Default")
      (node (ref "P1") (pin "PAD_PD2") (pinfunction "SD2_PAD_PD2") (pintype "bidirectional"))
      (node (ref "U1") (pin "15") (pinfunction "PA1_15") (pintype "bidirectional"))
    )
    (net (code "37") (name "UART4_TX") (class "Default")
      (node (ref "P1") (pin "PAD_PU2") (pinfunction "SU2_PAD_PU2") (pintype "bidirectional"))
      (node (ref "U1") (pin "14") (pinfunction "PA0_14") (pintype "bidirectional"))
    )
    (net (code "38") (name "UART5_RX") (class "Default")
      (node (ref "P1") (pin "PAD_PD8") (pinfunction "SD8_PAD_PD8") (pintype "bidirectional"))
      (node (ref "U1") (pin "56") (pinfunction "PB4_56") (pintype "bidirectional"))
    )
    (net (code "39") (name "UART5_TX") (class "Default")
      (node (ref "P1") (pin "PAD_PU8") (pinfunction "SU8_PAD_PU8") (pintype "bidirectional"))
      (node (ref "U1") (pin "55") (pinfunction "PB3_55") (pintype "bidirectional"))
    )
    (net (code "40") (name "UART6_RX") (class "Default")
      (node (ref "P1") (pin "PAD_PD10") (pinfunction "SD10_PAD_PD10") (pintype "bidirectional"))
      (node (ref "U1") (pin "21") (pinfunction "PA5_21") (pintype "bidirectional"))
    )
    (net (code "41") (name "UART6_TX") (class "Default")
      (node (ref "P1") (pin "PAD_PU10") (pinfunction "SU10_PAD_PU10") (pintype "bidirectional"))
      (node (ref "U1") (pin "20") (pinfunction "PA4_20") (pintype "bidirectional"))
    )
    (net (code "42") (name "UART7_RX") (class "Default")
      (node (ref "P1") (pin "PAD_PD9") (pinfunction "SD9_PAD_PD9") (pintype "bidirectional"))
      (node (ref "U1") (pin "9") (pinfunction "PC1_9") (pintype "bidirectional"))
    )
    (net (code "43") (name "UART7_TX") (class "Default")
      (node (ref "P1") (pin "PAD_PU9") (pinfunction "SU9_PAD_PU9") (pintype "bidirectional"))
      (node (ref "U1") (pin "8") (pinfunction "PC0_8") (pintype "bidirectional"))
    )
    (net (code "44") (name "UART8_RX") (class "Default")
      (node (ref "P1") (pin "PAD_PD1") (pinfunction "SD1_PAD_PD1") (pintype "bidirectional"))
      (node (ref "U1") (pin "11") (pinfunction "PC3_11") (pintype "bidirectional"))
    )
    (net (code "45") (name "UART8_TX") (class "Default")
      (node (ref "P1") (pin "PAD_PU1") (pinfunction "SU1_PAD_PU1") (pintype "bidirectional"))
      (node (ref "U1") (pin "10") (pinfunction "PC2_10") (pintype "bidirectional"))
    )
    (net (code "46") (name "VCC_RF") (class "Default")
      (node (ref "C19") (pin "2") (pinfunction "2_2") (pintype "passive"))
      (node (ref "R12") (pin "1") (pinfunction "1_1") (pintype "passive"))
      (node (ref "R7") (pin "2") (pinfunction "2_2") (pintype "passive"))
      (node (ref "R8") (pin "2") (pinfunction "2_2") (pintype "passive"))
      (node (ref "U4") (pin "14") (pinfunction "VCC_RF_14") (pintype "bidirectional"))
    )
    (net (code "47") (name "VDD") (class "Default")
      (node (ref "C1") (pin "1") (pinfunction "1_1") (pintype "passive"))
      (node (ref "C11") (pin "2") (pinfunction "2_2") (pintype "passive"))
      (node (ref "C2") (pin "1") (pinfunction "+_1") (pintype "passive"))
      (node (ref "C3") (pin "1") (pinfunction "1_1") (pintype "passive"))
      (node (ref "C4") (pin "1") (pinfunction "+_1") (pintype "passive"))
      (node (ref "C5") (pin "1") (pinfunction "1_1") (pintype "passive"))
      (node (ref "C6") (pin "1") (pinfunction "1_1") (pintype "passive"))
      (node (ref "C7") (pin "1") (pinfunction "+_1") (pintype "passive"))
      (node (ref "C9") (pin "1") (pinfunction "1_1") (pintype "passive"))
      (node (ref "FB4") (pin "2") (pinfunction "2_2") (pintype "passive"))
      (node (ref "P1") (pin "PAD_PU11") (pinfunction "VDD1_PAD_PU11") (pintype "power_in"))
      (node (ref "P1") (pin "PAD_PU12") (pinfunction "VDD2_PAD_PU12") (pintype "power_in"))
      (node (ref "P1") (pin "PAD_PU13") (pinfunction "VDD3_PAD_PU13") (pintype "power_in"))
      (node (ref "P1") (pin "PAD_PU14") (pinfunction "VDD4_PAD_PU14") (pintype "power_in"))
      (node (ref "P1") (pin "PAD_PU15") (pinfunction "VDD5_PAD_PU15") (pintype "power_in"))
      (node (ref "P1") (pin "PAD_PU16") (pinfunction "VDD6_PAD_PU16") (pintype "power_in"))
      (node (ref "P1") (pin "PAD_PU17") (pinfunction "VDD7_PAD_PU17") (pintype "power_in"))
      (node (ref "P1") (pin "PAD_PU18") (pinfunction "VDD8_PAD_PU18") (pintype "power_in"))
      (node (ref "P1") (pin "PAD_PU19") (pinfunction "VDD9_PAD_PU19") (pintype "power_in"))
      (node (ref "P1") (pin "PAD_PU20") (pinfunction "VDD10_PAD_PU20") (pintype "power_in"))
      (node (ref "U1") (pin "1") (pinfunction "VBAT_1") (pintype "power_in"))
      (node (ref "U1") (pin "13") (pinfunction "VDDA_13") (pintype "power_in"))
      (node (ref "U1") (pin "19") (pinfunction "1_VDD_19") (pintype "power_in"))
      (node (ref "U1") (pin "32") (pinfunction "2_VDD_32") (pintype "power_in"))
      (node (ref "U1") (pin "48") (pinfunction "VDDIO2_48") (pintype "power_in"))
      (node (ref "U1") (pin "64") (pinfunction "3_VDD_64") (pintype "power_in"))
    )
    (net (code "48") (name "unconnected-(P1-SD4-PadPAD_PD4)") (class "Default")
      (node (ref "P1") (pin "PAD_PD4") (pinfunction "SD4_PAD_PD4") (pintype "bidirectional"))
    )
    (net (code "49") (name "unconnected-(P1-SD6-PadPAD_PD6)") (class "Default")
      (node (ref "P1") (pin "PAD_PD6") (pinfunction "SD6_PAD_PD6") (pintype "bidirectional"))
    )
    (net (code "50") (name "unconnected-(P1-SU4-PadPAD_PU4)") (class "Default")
      (node (ref "P1") (pin "PAD_PU4") (pinfunction "SU4_PAD_PU4") (pintype "bidirectional"))
    )
    (net (code "51") (name "unconnected-(P1-SU6-PadPAD_PU6)") (class "Default")
      (node (ref "P1") (pin "PAD_PU6") (pinfunction "SU6_PAD_PU6") (pintype "bidirectional"))
    )
    (net (code "52") (name "unconnected-(U1-PA7-Pad23)") (class "Default")
      (node (ref "U1") (pin "23") (pinfunction "PA7_23") (pintype "bidirectional"))
    )
    (net (code "53") (name "unconnected-(U1-PA12-Pad45)") (class "Default")
      (node (ref "U1") (pin "45") (pinfunction "PA12_45") (pintype "bidirectional"))
    )
    (net (code "54") (name "unconnected-(U1-PA15-Pad50)") (class "Default")
      (node (ref "U1") (pin "50") (pinfunction "PA15_50") (pintype "bidirectional"))
    )
    (net (code "55") (name "unconnected-(U1-PB0-Pad26)") (class "Default")
      (node (ref "U1") (pin "26") (pinfunction "PB0_26") (pintype "bidirectional"))
    )
    (net (code "56") (name "unconnected-(U1-PB1-Pad27)") (class "Default")
      (node (ref "U1") (pin "27") (pinfunction "PB1_27") (pintype "bidirectional"))
    )
    (net (code "57") (name "unconnected-(U1-PB2-Pad28)") (class "Default")
      (node (ref "U1") (pin "28") (pinfunction "PB2_28") (pintype "bidirectional"))
    )
    (net (code "58") (name "unconnected-(U1-PB5-Pad57)") (class "Default")
      (node (ref "U1") (pin "57") (pinfunction "PB5_57") (pintype "bidirectional"))
    )
    (net (code "59") (name "unconnected-(U1-PB6-Pad58)") (class "Default")
      (node (ref "U1") (pin "58") (pinfunction "PB6_58") (pintype "bidirectional"))
    )
    (net (code "60") (name "unconnected-(U1-PB7-Pad59)") (class "Default")
      (node (ref "U1") (pin "59") (pinfunction "PB7_59") (pintype "bidirectional"))
    )
    (net (code "61") (name "unconnected-(U1-PB8-Pad61)") (class "Default")
      (node (ref "U1") (pin "61") (pinfunction "PB8_61") (pintype "bidirectional"))
    )
    (net (code "62") (name "unconnected-(U1-PB9-Pad62)") (class "Default")
      (node (ref "U1") (pin "62") (pinfunction "PB9_62") (pintype "bidirectional"))
    )
    (net (code "63") (name "unconnected-(U1-PB12-Pad33)") (class "Default")
      (node (ref "U1") (pin "33") (pinfunction "PB12_33") (pintype "bidirectional"))
    )
    (net (code "64") (name "unconnected-(U1-PB15-Pad36)") (class "Default")
      (node (ref "U1") (pin "36") (pinfunction "PB15_36") (pintype "bidirectional"))
    )
    (net (code "65") (name "unconnected-(U1-PC4-Pad24)") (class "Default")
      (node (ref "U1") (pin "24") (pinfunction "PC4_24") (pintype "bidirectional"))
    )
    (net (code "66") (name "unconnected-(U1-PC5-Pad25)") (class "Default")
      (node (ref "U1") (pin "25") (pinfunction "PC5_25") (pintype "bidirectional"))
    )
    (net (code "67") (name "unconnected-(U1-PC6-Pad37)") (class "Default")
      (node (ref "U1") (pin "37") (pinfunction "PC6_37") (pintype "bidirectional"))
    )
    (net (code "68") (name "unconnected-(U1-PC7-Pad38)") (class "Default")
      (node (ref "U1") (pin "38") (pinfunction "PC7_38") (pintype "bidirectional"))
    )
    (net (code "69") (name "unconnected-(U1-PC8-Pad39)") (class "Default")
      (node (ref "U1") (pin "39") (pinfunction "PC8_39") (pintype "bidirectional"))
    )
    (net (code "70") (name "unconnected-(U1-PC9-Pad40)") (class "Default")
      (node (ref "U1") (pin "40") (pinfunction "PC9_40") (pintype "bidirectional"))
    )
    (net (code "71") (name "unconnected-(U1-PC10-Pad51)") (class "Default")
      (node (ref "U1") (pin "51") (pinfunction "PC10_51") (pintype "bidirectional"))
    )
    (net (code "72") (name "unconnected-(U1-PC11-Pad52)") (class "Default")
      (node (ref "U1") (pin "52") (pinfunction "PC11_52") (pintype "bidirectional"))
    )
    (net (code "73") (name "unconnected-(U1-PC12-Pad53)") (class "Default")
      (node (ref "U1") (pin "53") (pinfunction "PC12_53") (pintype "bidirectional"))
    )
    (net (code "74") (name "unconnected-(U1-PC13-Pad2)") (class "Default")
      (node (ref "U1") (pin "2") (pinfunction "PC13_2") (pintype "bidirectional"))
    )
    (net (code "75") (name "unconnected-(U1-PC14-OSC32_IN(PC14)-Pad3)") (class "Default")
      (node (ref "U1") (pin "3") (pinfunction "PC14-OSC32_IN(PC14)_3") (pintype "bidirectional"))
    )
    (net (code "76") (name "unconnected-(U1-PC15-OSC32_OUT(PC15)-Pad4)") (class "Default")
      (node (ref "U1") (pin "4") (pinfunction "PC15-OSC32_OUT(PC15)_4") (pintype "bidirectional"))
    )
    (net (code "77") (name "unconnected-(U1-PD2-Pad54)") (class "Default")
      (node (ref "U1") (pin "54") (pinfunction "PD2_54") (pintype "bidirectional"))
    )
    (net (code "78") (name "unconnected-(U4-1PPS-Pad4)") (class "Default")
      (node (ref "U4") (pin "4") (pinfunction "1PPS_4") (pintype "bidirectional"))
    )
    (net (code "79") (name "unconnected-(U4-RESERVED_1-Pad15)") (class "Default")
      (node (ref "U4") (pin "15") (pinfunction "RESERVED_1_15") (pintype "bidirectional"))
    )
    (net (code "80") (name "unconnected-(U4-RESERVED_2-Pad18)") (class "Default")
      (node (ref "U4") (pin "18") (pinfunction "RESERVED_2_18") (pintype "bidirectional"))
    )
  )
)
